# AMS_Enerdel_Adapter_rev9.net
KiCad netlist of a schematic drawn in EAGLE
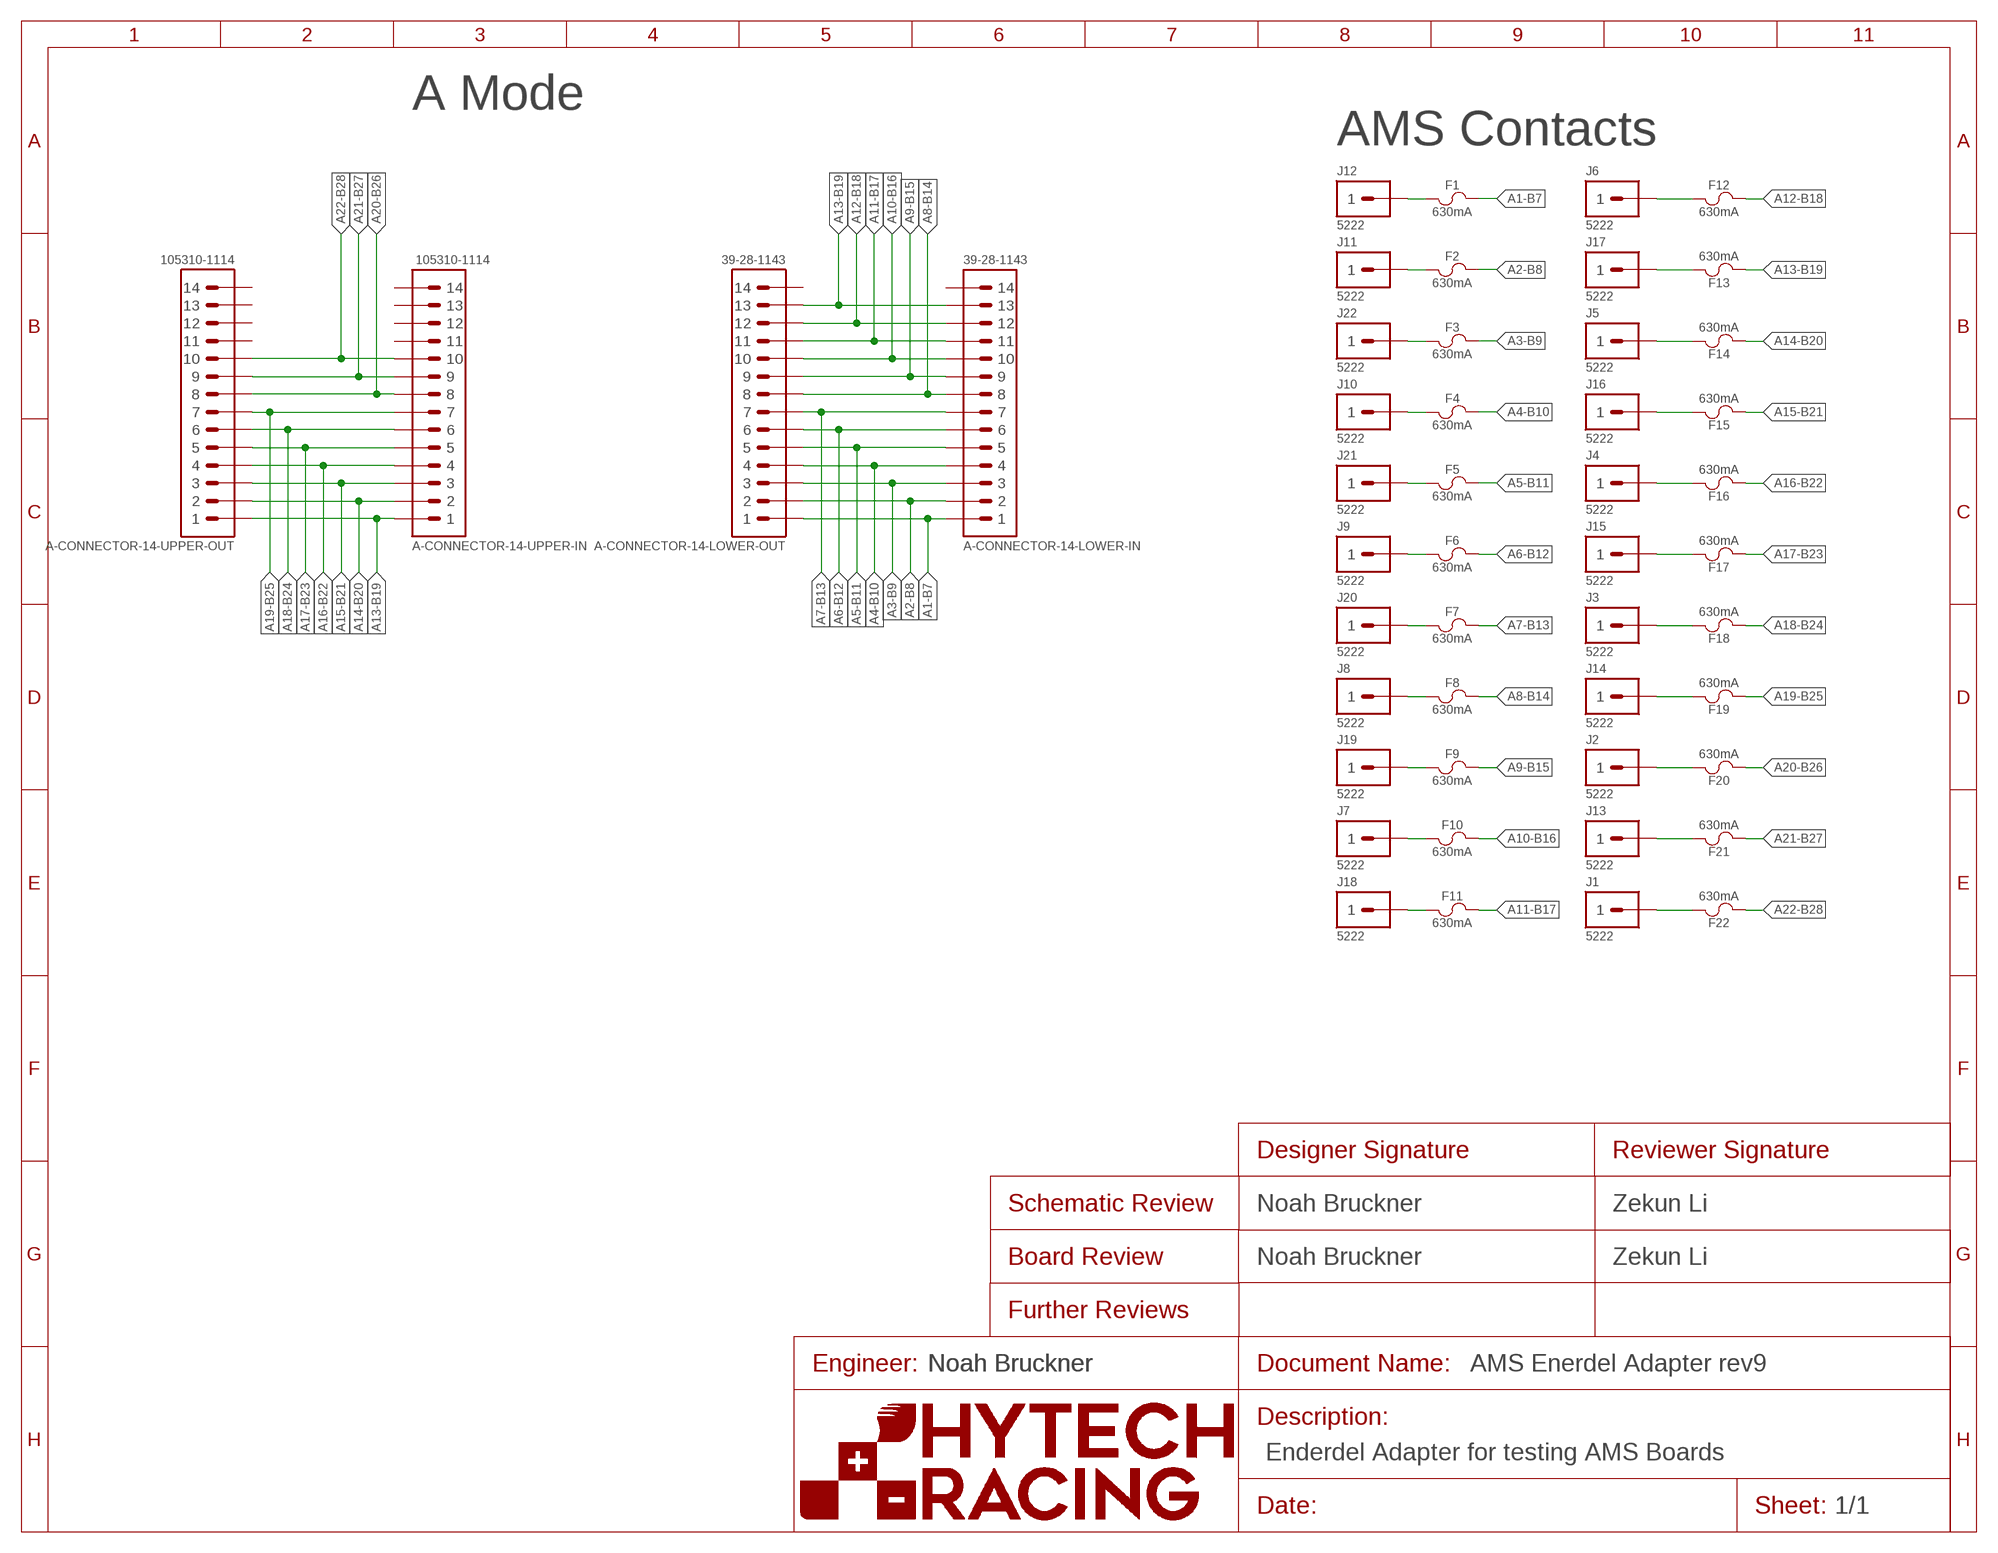
[diagram p0: schematic, sheet 1]

(export (version "E")
  (design (tool "Eeschema 10.0.6"))
  (components
    (comp (ref "A-CONNECTOR-14-LOWER-IN")
      (value "CONNECTOR-14_MINIFIT_")
      (footprint "eagle-import:MOLEX_MINIFIT_PTH_14")
      (fields (field (name "MPN") "39-28-1143"))
      (libsource (lib "eagle-import") (part "CONNECTOR-14_?_MINIFIT"))
    )
    (comp (ref "A-CONNECTOR-14-LOWER-OUT")
      (value "CONNECTOR-14_MINIFIT_")
      (footprint "eagle-import:MOLEX_MINIFIT_PTH_14")
      (fields (field (name "MPN") "39-28-1143"))
      (libsource (lib "eagle-import") (part "CONNECTOR-14_?_MINIFIT"))
    )
    (comp (ref "A-CONNECTOR-14-UPPER-IN")
      (value "CONNECTOR-14_NANOFIT_")
      (footprint "eagle-import:MOLEX_NANOFIT_PTH_14")
      (fields (field (name "MPN") " 105310-1114"))
      (libsource (lib "eagle-import") (part "CONNECTOR-14_?_NANOFIT"))
    )
    (comp (ref "A-CONNECTOR-14-UPPER-OUT")
      (value "CONNECTOR-14_NANOFIT_")
      (footprint "eagle-import:MOLEX_NANOFIT_PTH_14")
      (fields (field (name "MPN") "105310-1114"))
      (libsource (lib "eagle-import") (part "CONNECTOR-14_?_NANOFIT"))
    )
    (comp (ref "F1")
      (value "FUSE_OMF_125_.63A")
      (footprint "eagle-import:OMF_125")
      (fields
        (field (name "CURRENT") "630mA")
        (field (name "MANUFACTURER") "Schurter Inc.")
        (field (name "MPN") "3404.0008.11")
        (field (name "VOLTAGE") "125V")
      )
      (libsource (lib "eagle-import") (part "FUSE_?_OMF_125.63A"))
    )
    (comp (ref "F2")
      (value "FUSE_OMF_125_.63A")
      (footprint "eagle-import:OMF_125")
      (fields
        (field (name "CURRENT") "630mA")
        (field (name "MANUFACTURER") "Schurter Inc.")
        (field (name "MPN") "3404.0008.11")
        (field (name "VOLTAGE") "125V")
      )
      (libsource (lib "eagle-import") (part "FUSE_?_OMF_125.63A"))
    )
    (comp (ref "F3")
      (value "FUSE_OMF_125_.63A")
      (footprint "eagle-import:OMF_125")
      (fields
        (field (name "CURRENT") "630mA")
        (field (name "MANUFACTURER") "Schurter Inc.")
        (field (name "MPN") "3404.0008.11")
        (field (name "VOLTAGE") "125V")
      )
      (libsource (lib "eagle-import") (part "FUSE_?_OMF_125.63A"))
    )
    (comp (ref "F4")
      (value "FUSE_OMF_125_.63A")
      (footprint "eagle-import:OMF_125")
      (fields
        (field (name "CURRENT") "630mA")
        (field (name "MANUFACTURER") "Schurter Inc.")
        (field (name "MPN") "3404.0008.11")
        (field (name "VOLTAGE") "125V")
      )
      (libsource (lib "eagle-import") (part "FUSE_?_OMF_125.63A"))
    )
    (comp (ref "F5")
      (value "FUSE_OMF_125_.63A")
      (footprint "eagle-import:OMF_125")
      (fields
        (field (name "CURRENT") "630mA")
        (field (name "MANUFACTURER") "Schurter Inc.")
        (field (name "MPN") "3404.0008.11")
        (field (name "VOLTAGE") "125V")
      )
      (libsource (lib "eagle-import") (part "FUSE_?_OMF_125.63A"))
    )
    (comp (ref "F6")
      (value "FUSE_OMF_125_.63A")
      (footprint "eagle-import:OMF_125")
      (fields
        (field (name "CURRENT") "630mA")
        (field (name "MANUFACTURER") "Schurter Inc.")
        (field (name "MPN") "3404.0008.11")
        (field (name "VOLTAGE") "125V")
      )
      (libsource (lib "eagle-import") (part "FUSE_?_OMF_125.63A"))
    )
    (comp (ref "F7")
      (value "FUSE_OMF_125_.63A")
      (footprint "eagle-import:OMF_125")
      (fields
        (field (name "CURRENT") "630mA")
        (field (name "MANUFACTURER") "Schurter Inc.")
        (field (name "MPN") "3404.0008.11")
        (field (name "VOLTAGE") "125V")
      )
      (libsource (lib "eagle-import") (part "FUSE_?_OMF_125.63A"))
    )
    (comp (ref "F8")
      (value "FUSE_OMF_125_.63A")
      (footprint "eagle-import:OMF_125")
      (fields
        (field (name "CURRENT") "630mA")
        (field (name "MANUFACTURER") "Schurter Inc.")
        (field (name "MPN") "3404.0008.11")
        (field (name "VOLTAGE") "125V")
      )
      (libsource (lib "eagle-import") (part "FUSE_?_OMF_125.63A"))
    )
    (comp (ref "F9")
      (value "FUSE_OMF_125_.63A")
      (footprint "eagle-import:OMF_125")
      (fields
        (field (name "CURRENT") "630mA")
        (field (name "MANUFACTURER") "Schurter Inc.")
        (field (name "MPN") "3404.0008.11")
        (field (name "VOLTAGE") "125V")
      )
      (libsource (lib "eagle-import") (part "FUSE_?_OMF_125.63A"))
    )
    (comp (ref "F10")
      (value "FUSE_OMF_125_.63A")
      (footprint "eagle-import:OMF_125")
      (fields
        (field (name "CURRENT") "630mA")
        (field (name "MANUFACTURER") "Schurter Inc.")
        (field (name "MPN") "3404.0008.11")
        (field (name "VOLTAGE") "125V")
      )
      (libsource (lib "eagle-import") (part "FUSE_?_OMF_125.63A"))
    )
    (comp (ref "F11")
      (value "FUSE_OMF_125_.63A")
      (footprint "eagle-import:OMF_125")
      (fields
        (field (name "CURRENT") "630mA")
        (field (name "MANUFACTURER") "Schurter Inc.")
        (field (name "MPN") "3404.0008.11")
        (field (name "VOLTAGE") "125V")
      )
      (libsource (lib "eagle-import") (part "FUSE_?_OMF_125.63A"))
    )
    (comp (ref "F12")
      (value "FUSE_OMF_125_.63A")
      (footprint "eagle-import:OMF_125")
      (fields
        (field (name "CURRENT") "630mA")
        (field (name "MANUFACTURER") "Schurter Inc.")
        (field (name "MPN") "3404.0008.11")
        (field (name "VOLTAGE") "125V")
      )
      (libsource (lib "eagle-import") (part "FUSE_?_OMF_125.63A"))
    )
    (comp (ref "F13")
      (value "FUSE_OMF_125_.63A")
      (footprint "eagle-import:OMF_125")
      (fields
        (field (name "CURRENT") "630mA")
        (field (name "MANUFACTURER") "Schurter Inc.")
        (field (name "MPN") "3404.0008.11")
        (field (name "VOLTAGE") "125V")
      )
      (libsource (lib "eagle-import") (part "FUSE_?_OMF_125.63A"))
    )
    (comp (ref "F14")
      (value "FUSE_OMF_125_.63A")
      (footprint "eagle-import:OMF_125")
      (fields
        (field (name "CURRENT") "630mA")
        (field (name "MANUFACTURER") "Schurter Inc.")
        (field (name "MPN") "3404.0008.11")
        (field (name "VOLTAGE") "125V")
      )
      (libsource (lib "eagle-import") (part "FUSE_?_OMF_125.63A"))
    )
    (comp (ref "F15")
      (value "FUSE_OMF_125_.63A")
      (footprint "eagle-import:OMF_125")
      (fields
        (field (name "CURRENT") "630mA")
        (field (name "MANUFACTURER") "Schurter Inc.")
        (field (name "MPN") "3404.0008.11")
        (field (name "VOLTAGE") "125V")
      )
      (libsource (lib "eagle-import") (part "FUSE_?_OMF_125.63A"))
    )
    (comp (ref "F16")
      (value "FUSE_OMF_125_.63A")
      (footprint "eagle-import:OMF_125")
      (fields
        (field (name "CURRENT") "630mA")
        (field (name "MANUFACTURER") "Schurter Inc.")
        (field (name "MPN") "3404.0008.11")
        (field (name "VOLTAGE") "125V")
      )
      (libsource (lib "eagle-import") (part "FUSE_?_OMF_125.63A"))
    )
    (comp (ref "F17")
      (value "FUSE_OMF_125_.63A")
      (footprint "eagle-import:OMF_125")
      (fields
        (field (name "CURRENT") "630mA")
        (field (name "MANUFACTURER") "Schurter Inc.")
        (field (name "MPN") "3404.0008.11")
        (field (name "VOLTAGE") "125V")
      )
      (libsource (lib "eagle-import") (part "FUSE_?_OMF_125.63A"))
    )
    (comp (ref "F18")
      (value "FUSE_OMF_125_.63A")
      (footprint "eagle-import:OMF_125")
      (fields
        (field (name "CURRENT") "630mA")
        (field (name "MANUFACTURER") "Schurter Inc.")
        (field (name "MPN") "3404.0008.11")
        (field (name "VOLTAGE") "125V")
      )
      (libsource (lib "eagle-import") (part "FUSE_?_OMF_125.63A"))
    )
    (comp (ref "F19")
      (value "FUSE_OMF_125_.63A")
      (footprint "eagle-import:OMF_125")
      (fields
        (field (name "CURRENT") "630mA")
        (field (name "MANUFACTURER") "Schurter Inc.")
        (field (name "MPN") "3404.0008.11")
        (field (name "VOLTAGE") "125V")
      )
      (libsource (lib "eagle-import") (part "FUSE_?_OMF_125.63A"))
    )
    (comp (ref "F20")
      (value "FUSE_OMF_125_.63A")
      (footprint "eagle-import:OMF_125")
      (fields
        (field (name "CURRENT") "630mA")
        (field (name "MANUFACTURER") "Schurter Inc.")
        (field (name "MPN") "3404.0008.11")
        (field (name "VOLTAGE") "125V")
      )
      (libsource (lib "eagle-import") (part "FUSE_?_OMF_125.63A"))
    )
    (comp (ref "F21")
      (value "FUSE_OMF_125_.63A")
      (footprint "eagle-import:OMF_125")
      (fields
        (field (name "CURRENT") "630mA")
        (field (name "MANUFACTURER") "Schurter Inc.")
        (field (name "MPN") "3404.0008.11")
        (field (name "VOLTAGE") "125V")
      )
      (libsource (lib "eagle-import") (part "FUSE_?_OMF_125.63A"))
    )
    (comp (ref "F22")
      (value "FUSE_OMF_125_.63A")
      (footprint "eagle-import:OMF_125")
      (fields
        (field (name "CURRENT") "630mA")
        (field (name "MANUFACTURER") "Schurter Inc.")
        (field (name "MPN") "3404.0008.11")
        (field (name "VOLTAGE") "125V")
      )
      (libsource (lib "eagle-import") (part "FUSE_?_OMF_125.63A"))
    )
    (comp (ref "J1")
      (value "CONNECTOR-1_5222")
      (footprint "eagle-import:5222")
      (fields (field (name "MPN") "5222") (field (name "MANUFACTURER") "Keystone Electronics"))
      (libsource (lib "eagle-import") (part "CONNECTOR-1_?5222"))
    )
    (comp (ref "J2")
      (value "CONNECTOR-1_5222")
      (footprint "eagle-import:5222")
      (fields (field (name "MPN") "5222") (field (name "MANUFACTURER") "Keystone Electronics"))
      (libsource (lib "eagle-import") (part "CONNECTOR-1_?5222"))
    )
    (comp (ref "J3")
      (value "CONNECTOR-1_5222")
      (footprint "eagle-import:5222")
      (fields (field (name "MPN") "5222") (field (name "MANUFACTURER") "Keystone Electronics"))
      (libsource (lib "eagle-import") (part "CONNECTOR-1_?5222"))
    )
    (comp (ref "J4")
      (value "CONNECTOR-1_5222")
      (footprint "eagle-import:5222")
      (fields (field (name "MPN") "5222") (field (name "MANUFACTURER") "Keystone Electronics"))
      (libsource (lib "eagle-import") (part "CONNECTOR-1_?5222"))
    )
    (comp (ref "J5")
      (value "CONNECTOR-1_5222")
      (footprint "eagle-import:5222")
      (fields (field (name "MPN") "5222") (field (name "MANUFACTURER") "Keystone Electronics"))
      (libsource (lib "eagle-import") (part "CONNECTOR-1_?5222"))
    )
    (comp (ref "J6")
      (value "CONNECTOR-1_5222")
      (footprint "eagle-import:5222")
      (fields (field (name "MPN") "5222") (field (name "MANUFACTURER") "Keystone Electronics"))
      (libsource (lib "eagle-import") (part "CONNECTOR-1_?5222"))
    )
    (comp (ref "J7")
      (value "CONNECTOR-1_5222")
      (footprint "eagle-import:5222")
      (fields (field (name "MPN") "5222") (field (name "MANUFACTURER") "Keystone Electronics"))
      (libsource (lib "eagle-import") (part "CONNECTOR-1_?5222"))
    )
    (comp (ref "J8")
      (value "CONNECTOR-1_5222")
      (footprint "eagle-import:5222")
      (fields (field (name "MPN") "5222") (field (name "MANUFACTURER") "Keystone Electronics"))
      (libsource (lib "eagle-import") (part "CONNECTOR-1_?5222"))
    )
    (comp (ref "J9")
      (value "CONNECTOR-1_5222")
      (footprint "eagle-import:5222")
      (fields (field (name "MPN") "5222") (field (name "MANUFACTURER") "Keystone Electronics"))
      (libsource (lib "eagle-import") (part "CONNECTOR-1_?5222"))
    )
    (comp (ref "J10")
      (value "CONNECTOR-1_5222")
      (footprint "eagle-import:5222")
      (fields (field (name "MPN") "5222") (field (name "MANUFACTURER") "Keystone Electronics"))
      (libsource (lib "eagle-import") (part "CONNECTOR-1_?5222"))
    )
    (comp (ref "J11")
      (value "CONNECTOR-1_5222")
      (footprint "eagle-import:5222")
      (fields (field (name "MPN") "5222") (field (name "MANUFACTURER") "Keystone Electronics"))
      (libsource (lib "eagle-import") (part "CONNECTOR-1_?5222"))
    )
    (comp (ref "J12")
      (value "CONNECTOR-1_5222")
      (footprint "eagle-import:5222")
      (fields (field (name "MPN") "5222") (field (name "MANUFACTURER") "Keystone Electronics"))
      (libsource (lib "eagle-import") (part "CONNECTOR-1_?5222"))
    )
    (comp (ref "J13")
      (value "CONNECTOR-1_5222")
      (footprint "eagle-import:5222")
      (fields (field (name "MPN") "5222") (field (name "MANUFACTURER") "Keystone Electronics"))
      (libsource (lib "eagle-import") (part "CONNECTOR-1_?5222"))
    )
    (comp (ref "J14")
      (value "CONNECTOR-1_5222")
      (footprint "eagle-import:5222")
      (fields (field (name "MPN") "5222") (field (name "MANUFACTURER") "Keystone Electronics"))
      (libsource (lib "eagle-import") (part "CONNECTOR-1_?5222"))
    )
    (comp (ref "J15")
      (value "CONNECTOR-1_5222")
      (footprint "eagle-import:5222")
      (fields (field (name "MPN") "5222") (field (name "MANUFACTURER") "Keystone Electronics"))
      (libsource (lib "eagle-import") (part "CONNECTOR-1_?5222"))
    )
    (comp (ref "J16")
      (value "CONNECTOR-1_5222")
      (footprint "eagle-import:5222")
      (fields (field (name "MPN") "5222") (field (name "MANUFACTURER") "Keystone Electronics"))
      (libsource (lib "eagle-import") (part "CONNECTOR-1_?5222"))
    )
    (comp (ref "J17")
      (value "CONNECTOR-1_5222")
      (footprint "eagle-import:5222")
      (fields (field (name "MPN") "5222") (field (name "MANUFACTURER") "Keystone Electronics"))
      (libsource (lib "eagle-import") (part "CONNECTOR-1_?5222"))
    )
    (comp (ref "J18")
      (value "CONNECTOR-1_5222")
      (footprint "eagle-import:5222")
      (fields (field (name "MPN") "5222") (field (name "MANUFACTURER") "Keystone Electronics"))
      (libsource (lib "eagle-import") (part "CONNECTOR-1_?5222"))
    )
    (comp (ref "J19")
      (value "CONNECTOR-1_5222")
      (footprint "eagle-import:5222")
      (fields (field (name "MPN") "5222") (field (name "MANUFACTURER") "Keystone Electronics"))
      (libsource (lib "eagle-import") (part "CONNECTOR-1_?5222"))
    )
    (comp (ref "J20")
      (value "CONNECTOR-1_5222")
      (footprint "eagle-import:5222")
      (fields (field (name "MPN") "5222") (field (name "MANUFACTURER") "Keystone Electronics"))
      (libsource (lib "eagle-import") (part "CONNECTOR-1_?5222"))
    )
    (comp (ref "J21")
      (value "CONNECTOR-1_5222")
      (footprint "eagle-import:5222")
      (fields (field (name "MPN") "5222") (field (name "MANUFACTURER") "Keystone Electronics"))
      (libsource (lib "eagle-import") (part "CONNECTOR-1_?5222"))
    )
    (comp (ref "J22")
      (value "CONNECTOR-1_5222")
      (footprint "eagle-import:5222")
      (fields (field (name "MPN") "5222") (field (name "MANUFACTURER") "Keystone Electronics"))
      (libsource (lib "eagle-import") (part "CONNECTOR-1_?5222"))
    )
  )
  (nets
    (net (code "1") (name "A1-B7") (class "Default")
      (node (ref "A-CONNECTOR-14-LOWER-IN") (pin "1") (pinfunction "1_1") (pintype "passive"))
      (node (ref "A-CONNECTOR-14-LOWER-OUT") (pin "1") (pinfunction "1_1") (pintype "passive"))
      (node (ref "F1") (pin "2") (pinfunction "2_2") (pintype "passive"))
    )
    (net (code "2") (name "A2-B8") (class "Default")
      (node (ref "A-CONNECTOR-14-LOWER-IN") (pin "2") (pinfunction "2_2") (pintype "passive"))
      (node (ref "A-CONNECTOR-14-LOWER-OUT") (pin "2") (pinfunction "2_2") (pintype "passive"))
      (node (ref "F2") (pin "2") (pinfunction "2_2") (pintype "passive"))
    )
    (net (code "3") (name "A3-B9") (class "Default")
      (node (ref "A-CONNECTOR-14-LOWER-IN") (pin "3") (pinfunction "3_3") (pintype "passive"))
      (node (ref "A-CONNECTOR-14-LOWER-OUT") (pin "3") (pinfunction "3_3") (pintype "passive"))
      (node (ref "F3") (pin "2") (pinfunction "2_2") (pintype "passive"))
    )
    (net (code "4") (name "A4-B10") (class "Default")
      (node (ref "A-CONNECTOR-14-LOWER-IN") (pin "4") (pinfunction "4_4") (pintype "passive"))
      (node (ref "A-CONNECTOR-14-LOWER-OUT") (pin "4") (pinfunction "4_4") (pintype "passive"))
      (node (ref "F4") (pin "2") (pinfunction "2_2") (pintype "passive"))
    )
    (net (code "5") (name "A5-B11") (class "Default")
      (node (ref "A-CONNECTOR-14-LOWER-IN") (pin "5") (pinfunction "5_5") (pintype "passive"))
      (node (ref "A-CONNECTOR-14-LOWER-OUT") (pin "5") (pinfunction "5_5") (pintype "passive"))
      (node (ref "F5") (pin "2") (pinfunction "2_2") (pintype "passive"))
    )
    (net (code "6") (name "A6-B12") (class "Default")
      (node (ref "A-CONNECTOR-14-LOWER-IN") (pin "6") (pinfunction "6_6") (pintype "passive"))
      (node (ref "A-CONNECTOR-14-LOWER-OUT") (pin "6") (pinfunction "6_6") (pintype "passive"))
      (node (ref "F6") (pin "2") (pinfunction "2_2") (pintype "passive"))
    )
    (net (code "7") (name "A7-B13") (class "Default")
      (node (ref "A-CONNECTOR-14-LOWER-IN") (pin "7") (pinfunction "7_7") (pintype "passive"))
      (node (ref "A-CONNECTOR-14-LOWER-OUT") (pin "7") (pinfunction "7_7") (pintype "passive"))
      (node (ref "F7") (pin "2") (pinfunction "2_2") (pintype "passive"))
    )
    (net (code "8") (name "A8-B14") (class "Default")
      (node (ref "A-CONNECTOR-14-LOWER-IN") (pin "8") (pinfunction "8_8") (pintype "passive"))
      (node (ref "A-CONNECTOR-14-LOWER-OUT") (pin "8") (pinfunction "8_8") (pintype "passive"))
      (node (ref "F8") (pin "2") (pinfunction "2_2") (pintype "passive"))
    )
    (net (code "9") (name "A9-B15") (class "Default")
      (node (ref "A-CONNECTOR-14-LOWER-IN") (pin "9") (pinfunction "9_9") (pintype "passive"))
      (node (ref "A-CONNECTOR-14-LOWER-OUT") (pin "9") (pinfunction "9_9") (pintype "passive"))
      (node (ref "F9") (pin "2") (pinfunction "2_2") (pintype "passive"))
    )
    (net (code "10") (name "A10-B16") (class "Default")
      (node (ref "A-CONNECTOR-14-LOWER-IN") (pin "10") (pinfunction "10_10") (pintype "passive"))
      (node (ref "A-CONNECTOR-14-LOWER-OUT") (pin "10") (pinfunction "10_10") (pintype "passive"))
      (node (ref "F10") (pin "2") (pinfunction "2_2") (pintype "passive"))
    )
    (net (code "11") (name "A11-B17") (class "Default")
      (node (ref "A-CONNECTOR-14-LOWER-IN") (pin "11") (pinfunction "11_11") (pintype "passive"))
      (node (ref "A-CONNECTOR-14-LOWER-OUT") (pin "11") (pinfunction "11_11") (pintype "passive"))
      (node (ref "F11") (pin "2") (pinfunction "2_2") (pintype "passive"))
    )
    (net (code "12") (name "A12-B18") (class "Default")
      (node (ref "A-CONNECTOR-14-LOWER-IN") (pin "12") (pinfunction "12_12") (pintype "passive"))
      (node (ref "A-CONNECTOR-14-LOWER-OUT") (pin "12") (pinfunction "12_12") (pintype "passive"))
      (node (ref "F12") (pin "2") (pinfunction "2_2") (pintype "passive"))
    )
    (net (code "13") (name "A13-B19") (class "Default")
      (node (ref "A-CONNECTOR-14-LOWER-IN") (pin "13") (pinfunction "13_13") (pintype "passive"))
      (node (ref "A-CONNECTOR-14-LOWER-OUT") (pin "13") (pinfunction "13_13") (pintype "passive"))
      (node (ref "A-CONNECTOR-14-UPPER-IN") (pin "1") (pinfunction "1_1") (pintype "passive"))
      (node (ref "A-CONNECTOR-14-UPPER-OUT") (pin "1") (pinfunction "1_1") (pintype "passive"))
      (node (ref "F13") (pin "1") (pinfunction "1_1") (pintype "passive"))
    )
    (net (code "14") (name "A14-B20") (class "Default")
      (node (ref "A-CONNECTOR-14-UPPER-IN") (pin "2") (pinfunction "2_2") (pintype "passive"))
      (node (ref "A-CONNECTOR-14-UPPER-OUT") (pin "2") (pinfunction "2_2") (pintype "passive"))
      (node (ref "F14") (pin "1") (pinfunction "1_1") (pintype "passive"))
    )
    (net (code "15") (name "A15-B21") (class "Default")
      (node (ref "A-CONNECTOR-14-UPPER-IN") (pin "3") (pinfunction "3_3") (pintype "passive"))
      (node (ref "A-CONNECTOR-14-UPPER-OUT") (pin "3") (pinfunction "3_3") (pintype "passive"))
      (node (ref "F15") (pin "1") (pinfunction "1_1") (pintype "passive"))
    )
    (net (code "16") (name "A16-B22") (class "Default")
      (node (ref "A-CONNECTOR-14-UPPER-IN") (pin "4") (pinfunction "4_4") (pintype "passive"))
      (node (ref "A-CONNECTOR-14-UPPER-OUT") (pin "4") (pinfunction "4_4") (pintype "passive"))
      (node (ref "F16") (pin "1") (pinfunction "1_1") (pintype "passive"))
    )
    (net (code "17") (name "A17-B23") (class "Default")
      (node (ref "A-CONNECTOR-14-UPPER-IN") (pin "5") (pinfunction "5_5") (pintype "passive"))
      (node (ref "A-CONNECTOR-14-UPPER-OUT") (pin "5") (pinfunction "5_5") (pintype "passive"))
      (node (ref "F17") (pin "1") (pinfunction "1_1") (pintype "passive"))
    )
    (net (code "18") (name "A18-B24") (class "Default")
      (node (ref "A-CONNECTOR-14-UPPER-IN") (pin "6") (pinfunction "6_6") (pintype "passive"))
      (node (ref "A-CONNECTOR-14-UPPER-OUT") (pin "6") (pinfunction "6_6") (pintype "passive"))
      (node (ref "F18") (pin "1") (pinfunction "1_1") (pintype "passive"))
    )
    (net (code "19") (name "A19-B25") (class "Default")
      (node (ref "A-CONNECTOR-14-UPPER-IN") (pin "7") (pinfunction "7_7") (pintype "passive"))
      (node (ref "A-CONNECTOR-14-UPPER-OUT") (pin "7") (pinfunction "7_7") (pintype "passive"))
      (node (ref "F19") (pin "1") (pinfunction "1_1") (pintype "passive"))
    )
    (net (code "20") (name "A20-B26") (class "Default")
      (node (ref "A-CONNECTOR-14-UPPER-IN") (pin "8") (pinfunction "8_8") (pintype "passive"))
      (node (ref "A-CONNECTOR-14-UPPER-OUT") (pin "8") (pinfunction "8_8") (pintype "passive"))
      (node (ref "F20") (pin "1") (pinfunction "1_1") (pintype "passive"))
    )
    (net (code "21") (name "A21-B27") (class "Default")
      (node (ref "A-CONNECTOR-14-UPPER-IN") (pin "9") (pinfunction "9_9") (pintype "passive"))
      (node (ref "A-CONNECTOR-14-UPPER-OUT") (pin "9") (pinfunction "9_9") (pintype "passive"))
      (node (ref "F21") (pin "1") (pinfunction "1_1") (pintype "passive"))
    )
    (net (code "22") (name "A22-B28") (class "Default")
      (node (ref "A-CONNECTOR-14-UPPER-IN") (pin "10") (pinfunction "10_10") (pintype "passive"))
      (node (ref "A-CONNECTOR-14-UPPER-OUT") (pin "10") (pinfunction "10_10") (pintype "passive"))
      (node (ref "F22") (pin "1") (pinfunction "1_1") (pintype "passive"))
    )
    (net (code "23") (name "Net-(F1-Pad1)") (class "Default")
      (node (ref "F1") (pin "1") (pinfunction "1_1") (pintype "passive"))
      (node (ref "J12") (pin "1") (pinfunction "1_1") (pintype "passive"))
    )
    (net (code "24") (name "Net-(F2-Pad1)") (class "Default")
      (node (ref "F2") (pin "1") (pinfunction "1_1") (pintype "passive"))
      (node (ref "J11") (pin "1") (pinfunction "1_1") (pintype "passive"))
    )
    (net (code "25") (name "Net-(F3-Pad1)") (class "Default")
      (node (ref "F3") (pin "1") (pinfunction "1_1") (pintype "passive"))
      (node (ref "J22") (pin "1") (pinfunction "1_1") (pintype "passive"))
    )
    (net (code "26") (name "Net-(F4-Pad1)") (class "Default")
      (node (ref "F4") (pin "1") (pinfunction "1_1") (pintype "passive"))
      (node (ref "J10") (pin "1") (pinfunction "1_1") (pintype "passive"))
    )
    (net (code "27") (name "Net-(F5-Pad1)") (class "Default")
      (node (ref "F5") (pin "1") (pinfunction "1_1") (pintype "passive"))
      (node (ref "J21") (pin "1") (pinfunction "1_1") (pintype "passive"))
    )
    (net (code "28") (name "Net-(F6-Pad1)") (class "Default")
      (node (ref "F6") (pin "1") (pinfunction "1_1") (pintype "passive"))
      (node (ref "J9") (pin "1") (pinfunction "1_1") (pintype "passive"))
    )
    (net (code "29") (name "Net-(F7-Pad1)") (class "Default")
      (node (ref "F7") (pin "1") (pinfunction "1_1") (pintype "passive"))
      (node (ref "J20") (pin "1") (pinfunction "1_1") (pintype "passive"))
    )
    (net (code "30") (name "Net-(F8-Pad1)") (class "Default")
      (node (ref "F8") (pin "1") (pinfunction "1_1") (pintype "passive"))
      (node (ref "J8") (pin "1") (pinfunction "1_1") (pintype "passive"))
    )
    (net (code "31") (name "Net-(F9-Pad1)") (class "Default")
      (node (ref "F9") (pin "1") (pinfunction "1_1") (pintype "passive"))
      (node (ref "J19") (pin "1") (pinfunction "1_1") (pintype "passive"))
    )
    (net (code "32") (name "Net-(F10-Pad1)") (class "Default")
      (node (ref "F10") (pin "1") (pinfunction "1_1") (pintype "passive"))
      (node (ref "J7") (pin "1") (pinfunction "1_1") (pintype "passive"))
    )
    (net (code "33") (name "Net-(F11-Pad1)") (class "Default")
      (node (ref "F11") (pin "1") (pinfunction "1_1") (pintype "passive"))
      (node (ref "J18") (pin "1") (pinfunction "1_1") (pintype "passive"))
    )
    (net (code "34") (name "Net-(F12-Pad1)") (class "Default")
      (node (ref "F12") (pin "1") (pinfunction "1_1") (pintype "passive"))
      (node (ref "J6") (pin "1") (pinfunction "1_1") (pintype "passive"))
    )
    (net (code "35") (name "Net-(F13-Pad2)") (class "Default")
      (node (ref "F13") (pin "2") (pinfunction "2_2") (pintype "passive"))
      (node (ref "J17") (pin "1") (pinfunction "1_1") (pintype "passive"))
    )
    (net (code "36") (name "Net-(F14-Pad2)") (class "Default")
      (node (ref "F14") (pin "2") (pinfunction "2_2") (pintype "passive"))
      (node (ref "J5") (pin "1") (pinfunction "1_1") (pintype "passive"))
    )
    (net (code "37") (name "Net-(F15-Pad2)") (class "Default")
      (node (ref "F15") (pin "2") (pinfunction "2_2") (pintype "passive"))
      (node (ref "J16") (pin "1") (pinfunction "1_1") (pintype "passive"))
    )
    (net (code "38") (name "Net-(F16-Pad2)") (class "Default")
      (node (ref "F16") (pin "2") (pinfunction "2_2") (pintype "passive"))
      (node (ref "J4") (pin "1") (pinfunction "1_1") (pintype "passive"))
    )
    (net (code "39") (name "Net-(F17-Pad2)") (class "Default")
      (node (ref "F17") (pin "2") (pinfunction "2_2") (pintype "passive"))
      (node (ref "J15") (pin "1") (pinfunction "1_1") (pintype "passive"))
    )
    (net (code "40") (name "Net-(F18-Pad2)") (class "Default")
      (node (ref "F18") (pin "2") (pinfunction "2_2") (pintype "passive"))
      (node (ref "J3") (pin "1") (pinfunction "1_1") (pintype "passive"))
    )
    (net (code "41") (name "Net-(F19-Pad2)") (class "Default")
      (node (ref "F19") (pin "2") (pinfunction "2_2") (pintype "passive"))
      (node (ref "J14") (pin "1") (pinfunction "1_1") (pintype "passive"))
    )
    (net (code "42") (name "Net-(F20-Pad2)") (class "Default")
      (node (ref "F20") (pin "2") (pinfunction "2_2") (pintype "passive"))
      (node (ref "J2") (pin "1") (pinfunction "1_1") (pintype "passive"))
    )
    (net (code "43") (name "Net-(F21-Pad2)") (class "Default")
      (node (ref "F21") (pin "2") (pinfunction "2_2") (pintype "passive"))
      (node (ref "J13") (pin "1") (pinfunction "1_1") (pintype "passive"))
    )
    (net (code "44") (name "Net-(F22-Pad2)") (class "Default")
      (node (ref "F22") (pin "2") (pinfunction "2_2") (pintype "passive"))
      (node (ref "J1") (pin "1") (pinfunction "1_1") (pintype "passive"))
    )
    (net (code "45") (name "unconnected-(A-CONNECTOR-14-LOWER-IN-Pad14)") (class "Default")
      (node (ref "A-CONNECTOR-14-LOWER-IN") (pin "14") (pinfunction "14_14") (pintype "passive"))
    )
    (net (code "46") (name "unconnected-(A-CONNECTOR-14-LOWER-OUT-Pad14)") (class "Default")
      (node (ref "A-CONNECTOR-14-LOWER-OUT") (pin "14") (pinfunction "14_14") (pintype "passive"))
    )
    (net (code "47") (name "unconnected-(A-CONNECTOR-14-UPPER-IN-Pad11)") (class "Default")
      (node (ref "A-CONNECTOR-14-UPPER-IN") (pin "11") (pinfunction "11_11") (pintype "passive"))
    )
    (net (code "48") (name "unconnected-(A-CONNECTOR-14-UPPER-IN-Pad12)") (class "Default")
      (node (ref "A-CONNECTOR-14-UPPER-IN") (pin "12") (pinfunction "12_12") (pintype "passive"))
    )
    (net (code "49") (name "unconnected-(A-CONNECTOR-14-UPPER-IN-Pad13)") (class "Default")
      (node (ref "A-CONNECTOR-14-UPPER-IN") (pin "13") (pinfunction "13_13") (pintype "passive"))
    )
    (net (code "50") (name "unconnected-(A-CONNECTOR-14-UPPER-IN-Pad14)") (class "Default")
      (node (ref "A-CONNECTOR-14-UPPER-IN") (pin "14") (pinfunction "14_14") (pintype "passive"))
    )
    (net (code "51") (name "unconnected-(A-CONNECTOR-14-UPPER-OUT-Pad11)") (class "Default")
      (node (ref "A-CONNECTOR-14-UPPER-OUT") (pin "11") (pinfunction "11_11") (pintype "passive"))
    )
    (net (code "52") (name "unconnected-(A-CONNECTOR-14-UPPER-OUT-Pad12)") (class "Default")
      (node (ref "A-CONNECTOR-14-UPPER-OUT") (pin "12") (pinfunction "12_12") (pintype "passive"))
    )
    (net (code "53") (name "unconnected-(A-CONNECTOR-14-UPPER-OUT-Pad13)") (class "Default")
      (node (ref "A-CONNECTOR-14-UPPER-OUT") (pin "13") (pinfunction "13_13") (pintype "passive"))
    )
    (net (code "54") (name "unconnected-(A-CONNECTOR-14-UPPER-OUT-Pad14)") (class "Default")
      (node (ref "A-CONNECTOR-14-UPPER-OUT") (pin "14") (pinfunction "14_14") (pintype "passive"))
    )
  )
)
